# Bluetooth.net
KiCad netlist of a schematic drawn in Altium Designer
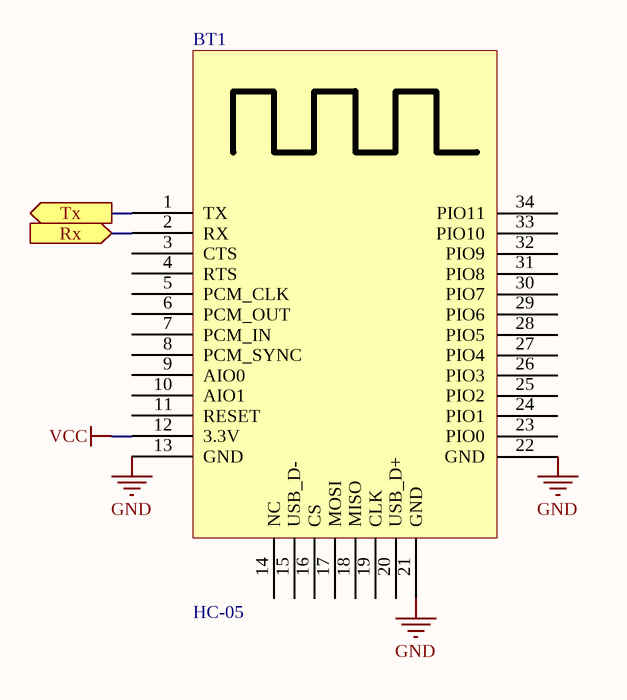
[diagram p0: Bluetooth.SchDoc]

(export (version "E")
  (design (tool "Eeschema 10.0.6"))
  (components
    (comp (ref "BT1") (value "HC-05") (footprint "HC-05") (libsource (lib "Salman_lib") (part "HC-05")))
  )
  (nets
    (net (code "1") (name "/Rx") (class "Default")
      (node (ref "BT1") (pin "2") (pinfunction "RX_2") (pintype "open_emitter"))
    )
    (net (code "2") (name "/Tx") (class "Default")
      (node (ref "BT1") (pin "1") (pinfunction "TX_1") (pintype "open_emitter"))
    )
    (net (code "3") (name "GND") (class "Default")
      (node (ref "BT1") (pin "13") (pinfunction "GND_13") (pintype "open_emitter"))
      (node (ref "BT1") (pin "21") (pinfunction "GND_21") (pintype "open_emitter"))
      (node (ref "BT1") (pin "22") (pinfunction "GND_22") (pintype "open_emitter"))
    )
    (net (code "4") (name "VCC") (class "Default")
      (node (ref "BT1") (pin "12") (pinfunction "3.3V_12") (pintype "open_emitter"))
    )
    (net (code "5") (name "unconnected-(BT1-AIO0-Pad9)") (class "Default")
      (node (ref "BT1") (pin "9") (pinfunction "AIO0_9") (pintype "open_emitter"))
    )
    (net (code "6") (name "unconnected-(BT1-AIO1-Pad10)") (class "Default")
      (node (ref "BT1") (pin "10") (pinfunction "AIO1_10") (pintype "open_emitter"))
    )
    (net (code "7") (name "unconnected-(BT1-CLK-Pad19)") (class "Default")
      (node (ref "BT1") (pin "19") (pinfunction "CLK_19") (pintype "open_emitter"))
    )
    (net (code "8") (name "unconnected-(BT1-CS-Pad16)") (class "Default")
      (node (ref "BT1") (pin "16") (pinfunction "CS_16") (pintype "open_emitter"))
    )
    (net (code "9") (name "unconnected-(BT1-CTS-Pad3)") (class "Default")
      (node (ref "BT1") (pin "3") (pinfunction "CTS_3") (pintype "open_emitter"))
    )
    (net (code "10") (name "unconnected-(BT1-MISO-Pad18)") (class "Default")
      (node (ref "BT1") (pin "18") (pinfunction "MISO_18") (pintype "open_emitter"))
    )
    (net (code "11") (name "unconnected-(BT1-MOSI-Pad17)") (class "Default")
      (node (ref "BT1") (pin "17") (pinfunction "MOSI_17") (pintype "open_emitter"))
    )
    (net (code "12") (name "unconnected-(BT1-NC-Pad14)") (class "Default")
      (node (ref "BT1") (pin "14") (pinfunction "NC_14") (pintype "open_emitter"))
    )
    (net (code "13") (name "unconnected-(BT1-PCM_CLK-Pad5)") (class "Default")
      (node (ref "BT1") (pin "5") (pinfunction "PCM_CLK_5") (pintype "open_emitter"))
    )
    (net (code "14") (name "unconnected-(BT1-PCM_IN-Pad7)") (class "Default")
      (node (ref "BT1") (pin "7") (pinfunction "PCM_IN_7") (pintype "open_emitter"))
    )
    (net (code "15") (name "unconnected-(BT1-PCM_OUT-Pad6)") (class "Default")
      (node (ref "BT1") (pin "6") (pinfunction "PCM_OUT_6") (pintype "open_emitter"))
    )
    (net (code "16") (name "unconnected-(BT1-PCM_SYNC-Pad8)") (class "Default")
      (node (ref "BT1") (pin "8") (pinfunction "PCM_SYNC_8") (pintype "open_emitter"))
    )
    (net (code "17") (name "unconnected-(BT1-PIO0-Pad23)") (class "Default")
      (node (ref "BT1") (pin "23") (pinfunction "PIO0_23") (pintype "open_emitter"))
    )
    (net (code "18") (name "unconnected-(BT1-PIO1-Pad24)") (class "Default")
      (node (ref "BT1") (pin "24") (pinfunction "PIO1_24") (pintype "open_emitter"))
    )
    (net (code "19") (name "unconnected-(BT1-PIO2-Pad25)") (class "Default")
      (node (ref "BT1") (pin "25") (pinfunction "PIO2_25") (pintype "open_emitter"))
    )
    (net (code "20") (name "unconnected-(BT1-PIO3-Pad26)") (class "Default")
      (node (ref "BT1") (pin "26") (pinfunction "PIO3_26") (pintype "open_emitter"))
    )
    (net (code "21") (name "unconnected-(BT1-PIO4-Pad27)") (class "Default")
      (node (ref "BT1") (pin "27") (pinfunction "PIO4_27") (pintype "open_emitter"))
    )
    (net (code "22") (name "unconnected-(BT1-PIO5-Pad28)") (class "Default")
      (node (ref "BT1") (pin "28") (pinfunction "PIO5_28") (pintype "open_emitter"))
    )
    (net (code "23") (name "unconnected-(BT1-PIO6-Pad29)") (class "Default")
      (node (ref "BT1") (pin "29") (pinfunction "PIO6_29") (pintype "open_emitter"))
    )
    (net (code "24") (name "unconnected-(BT1-PIO7-Pad30)") (class "Default")
      (node (ref "BT1") (pin "30") (pinfunction "PIO7_30") (pintype "open_emitter"))
    )
    (net (code "25") (name "unconnected-(BT1-PIO8-Pad31)") (class "Default")
      (node (ref "BT1") (pin "31") (pinfunction "PIO8_31") (pintype "open_emitter"))
    )
    (net (code "26") (name "unconnected-(BT1-PIO9-Pad32)") (class "Default")
      (node (ref "BT1") (pin "32") (pinfunction "PIO9_32") (pintype "open_emitter"))
    )
    (net (code "27") (name "unconnected-(BT1-PIO10-Pad33)") (class "Default")
      (node (ref "BT1") (pin "33") (pinfunction "PIO10_33") (pintype "open_emitter"))
    )
    (net (code "28") (name "unconnected-(BT1-PIO11-Pad34)") (class "Default")
      (node (ref "BT1") (pin "34") (pinfunction "PIO11_34") (pintype "open_emitter"))
    )
    (net (code "29") (name "unconnected-(BT1-RESET-Pad11)") (class "Default")
      (node (ref "BT1") (pin "11") (pinfunction "RESET_11") (pintype "open_emitter"))
    )
    (net (code "30") (name "unconnected-(BT1-RTS-Pad4)") (class "Default")
      (node (ref "BT1") (pin "4") (pinfunction "RTS_4") (pintype "open_emitter"))
    )
    (net (code "31") (name "unconnected-(BT1-USB_D+-Pad20)") (class "Default")
      (node (ref "BT1") (pin "20") (pinfunction "USB_D+_20") (pintype "open_emitter"))
    )
    (net (code "32") (name "unconnected-(BT1-USB_D--Pad15)") (class "Default")
      (node (ref "BT1") (pin "15") (pinfunction "USB_D-_15") (pintype "open_emitter"))
    )
  )
)
